# SC8815.net
KiCad netlist of a schematic drawn in Altium Designer
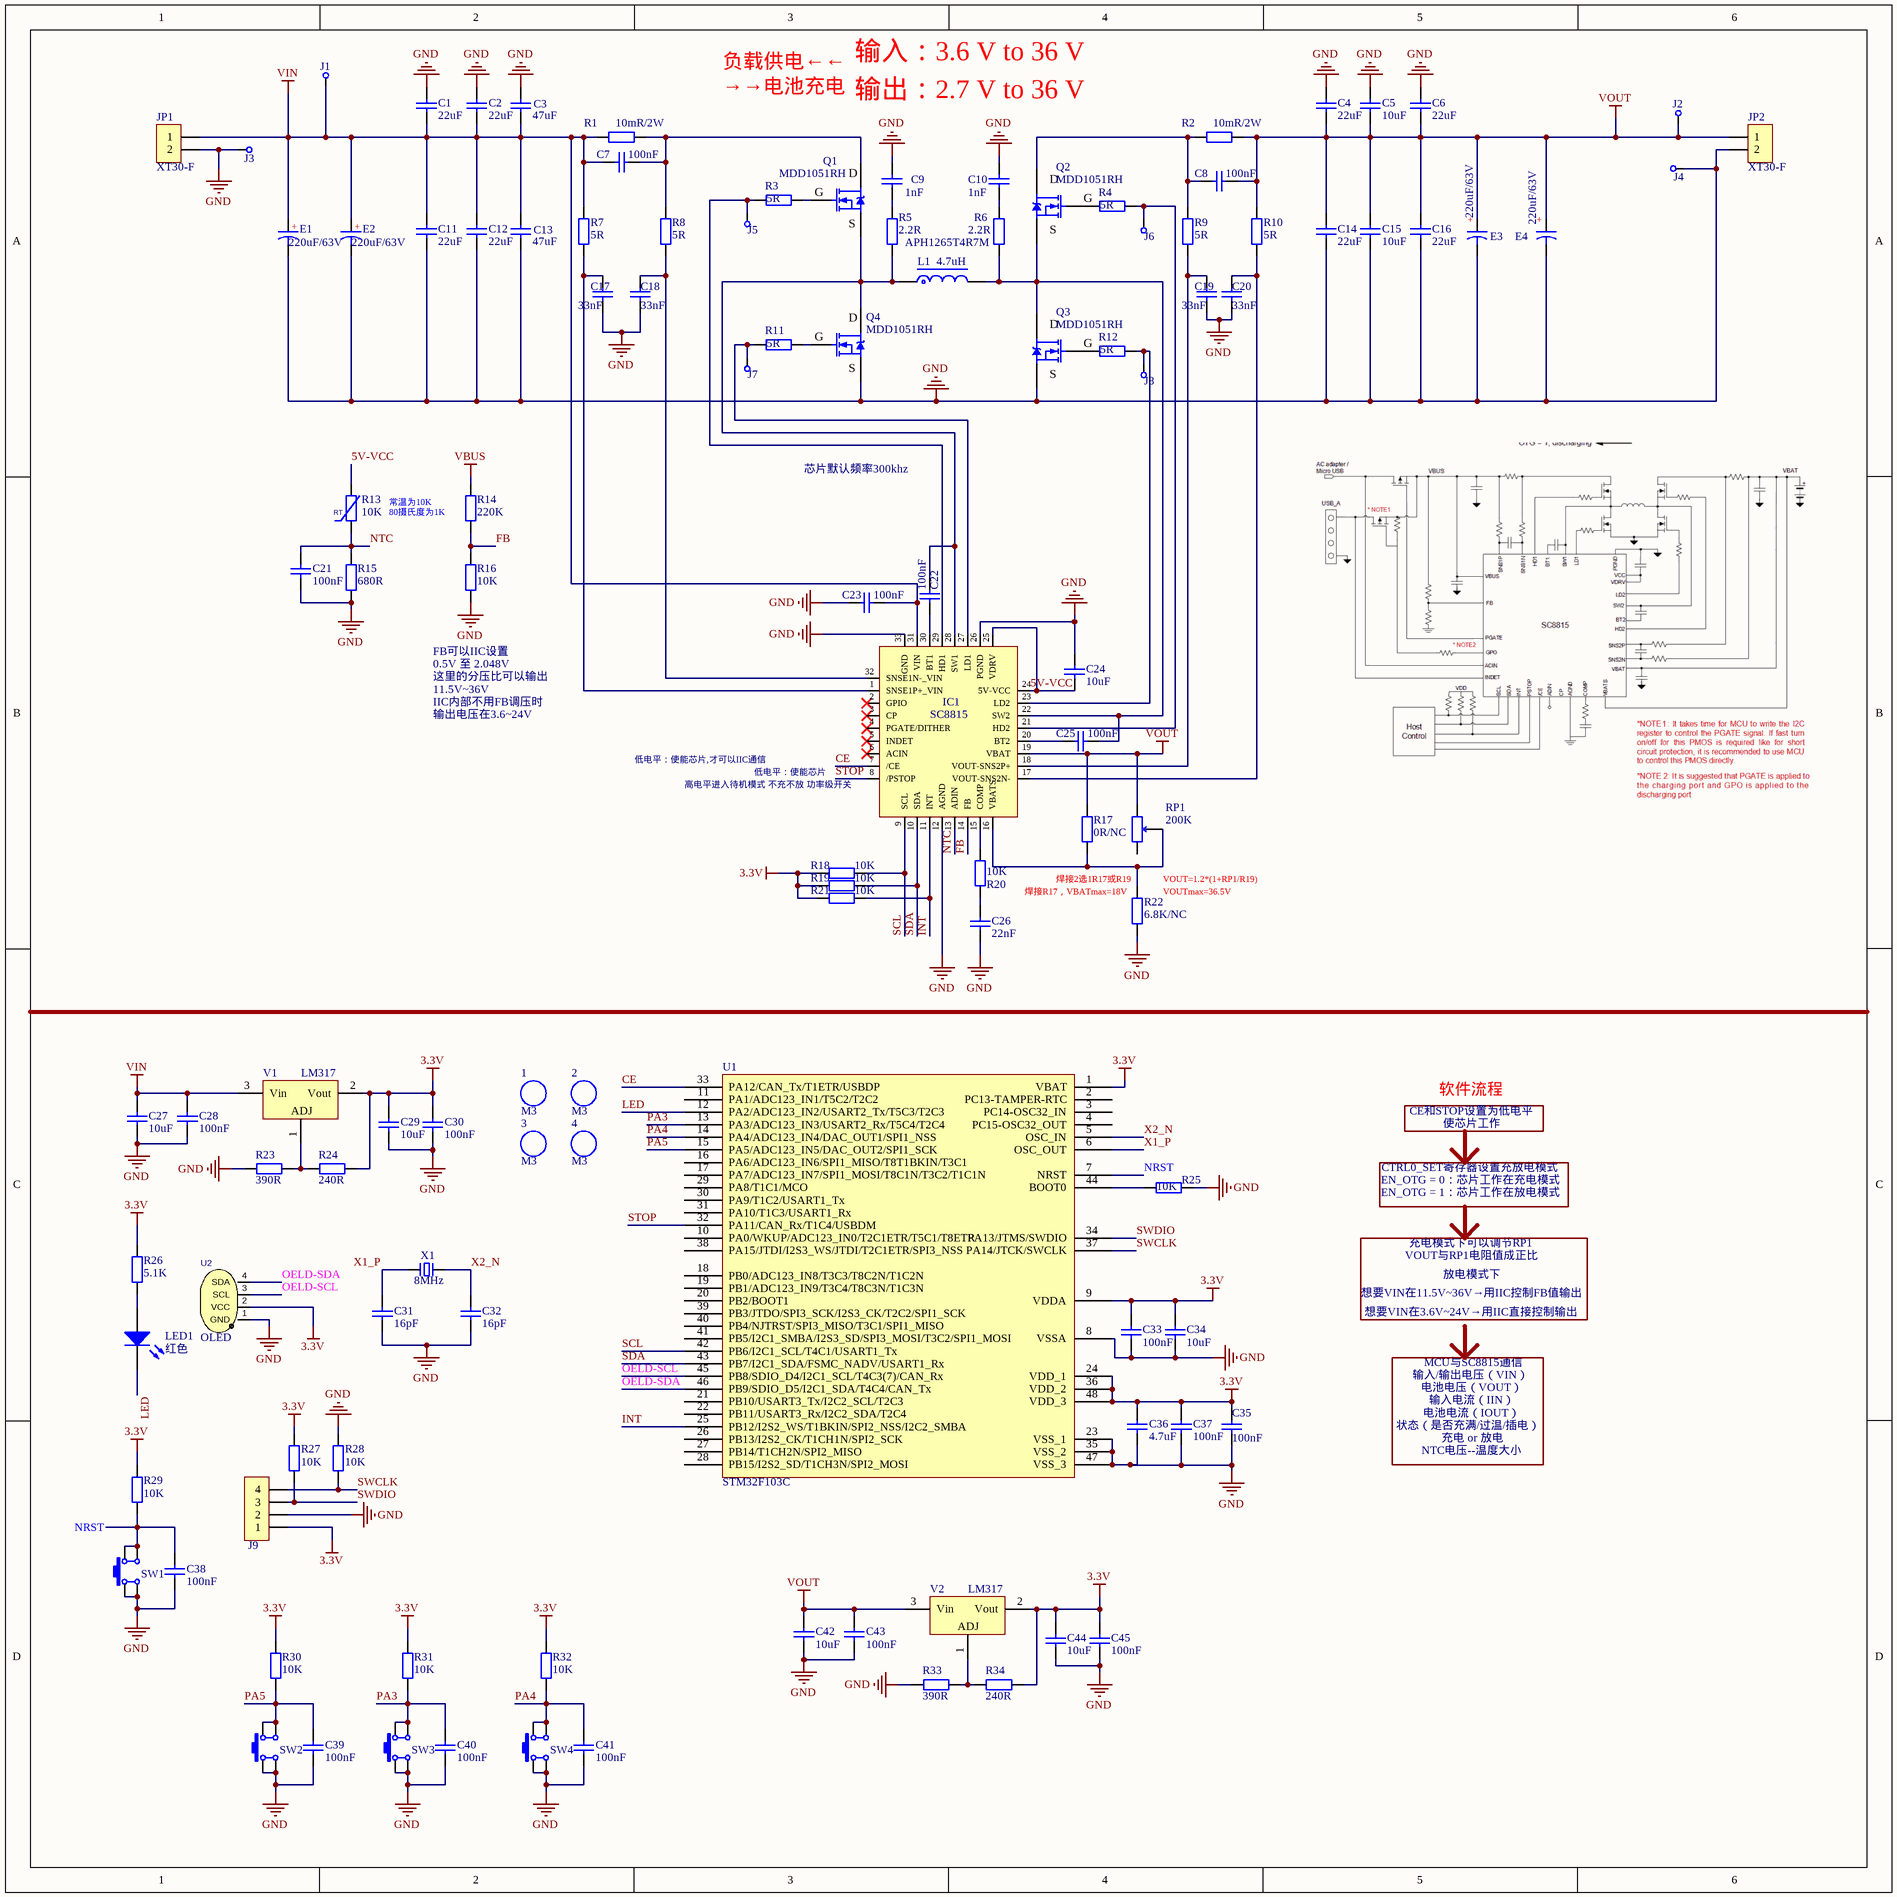
[diagram p0: SC8815.SchDoc]

(export (version "E")
  (design (tool "Eeschema 10.0.6"))
  (components
    (comp (ref "1")
      (value "M3")
      (footprint "M3 125X200")
      (description "铜柱孔")
      (libsource (lib "0.5 - 按键_开关_蜂鸣器_电池_测试点_Mark点_铜柱") (part "M3"))
    )
    (comp (ref "2")
      (value "M3")
      (footprint "M3 125X200")
      (description "铜柱孔")
      (libsource (lib "0.5 - 按键_开关_蜂鸣器_电池_测试点_Mark点_铜柱") (part "M3"))
    )
    (comp (ref "3")
      (value "M3")
      (footprint "M3 125X200")
      (description "铜柱孔")
      (libsource (lib "0.5 - 按键_开关_蜂鸣器_电池_测试点_Mark点_铜柱") (part "M3"))
    )
    (comp (ref "4")
      (value "M3")
      (footprint "M3 125X200")
      (description "铜柱孔")
      (libsource (lib "0.5 - 按键_开关_蜂鸣器_电池_测试点_Mark点_铜柱") (part "M3"))
    )
    (comp (ref "C1")
      (value "22uF")
      (footprint "C0805_L")
      (description "贴片电容/MLCC电容")
      (libsource (lib "0.1 - 电阻-电容-电感-保险丝-晶振-晶体-磁珠-电位器-法拉电容-馈通电容") (part "C"))
    )
    (comp (ref "C2")
      (value "22uF")
      (footprint "C0805_L")
      (description "贴片电容/MLCC电容")
      (libsource (lib "0.1 - 电阻-电容-电感-保险丝-晶振-晶体-磁珠-电位器-法拉电容-馈通电容") (part "C"))
    )
    (comp (ref "C3")
      (value "47uF")
      (footprint "C0805_L")
      (description "贴片电容/MLCC电容")
      (libsource (lib "0.1 - 电阻-电容-电感-保险丝-晶振-晶体-磁珠-电位器-法拉电容-馈通电容") (part "C"))
    )
    (comp (ref "C4")
      (value "22uF")
      (footprint "C0805_L")
      (description "贴片电容/MLCC电容")
      (libsource (lib "0.1 - 电阻-电容-电感-保险丝-晶振-晶体-磁珠-电位器-法拉电容-馈通电容") (part "C"))
    )
    (comp (ref "C5")
      (value "10uF")
      (footprint "C0805_L")
      (description "贴片电容/MLCC电容")
      (libsource (lib "0.1 - 电阻-电容-电感-保险丝-晶振-晶体-磁珠-电位器-法拉电容-馈通电容") (part "C"))
    )
    (comp (ref "C6")
      (value "22uF")
      (footprint "C0805_L")
      (description "贴片电容/MLCC电容")
      (libsource (lib "0.1 - 电阻-电容-电感-保险丝-晶振-晶体-磁珠-电位器-法拉电容-馈通电容") (part "C"))
    )
    (comp (ref "C7")
      (value "100nF")
      (footprint "C0805_L")
      (description "贴片电容/MLCC电容")
      (libsource (lib "0.1 - 电阻-电容-电感-保险丝-晶振-晶体-磁珠-电位器-法拉电容-馈通电容") (part "C"))
    )
    (comp (ref "C8")
      (value "100nF")
      (footprint "C0805_L")
      (description "贴片电容/MLCC电容")
      (libsource (lib "0.1 - 电阻-电容-电感-保险丝-晶振-晶体-磁珠-电位器-法拉电容-馈通电容") (part "C"))
    )
    (comp (ref "C9")
      (value "1nF")
      (footprint "C0805_L")
      (description "贴片电容/MLCC电容")
      (libsource (lib "0.1 - 电阻-电容-电感-保险丝-晶振-晶体-磁珠-电位器-法拉电容-馈通电容") (part "C"))
    )
    (comp (ref "C10")
      (value "1nF")
      (footprint "C0805_L")
      (description "贴片电容/MLCC电容")
      (libsource (lib "0.1 - 电阻-电容-电感-保险丝-晶振-晶体-磁珠-电位器-法拉电容-馈通电容") (part "C"))
    )
    (comp (ref "C11")
      (value "22uF")
      (footprint "C0805_L")
      (description "贴片电容/MLCC电容")
      (libsource (lib "0.1 - 电阻-电容-电感-保险丝-晶振-晶体-磁珠-电位器-法拉电容-馈通电容") (part "C"))
    )
    (comp (ref "C12")
      (value "22uF")
      (footprint "C0805_L")
      (description "贴片电容/MLCC电容")
      (libsource (lib "0.1 - 电阻-电容-电感-保险丝-晶振-晶体-磁珠-电位器-法拉电容-馈通电容") (part "C"))
    )
    (comp (ref "C13")
      (value "47uF")
      (footprint "C0805_L")
      (description "贴片电容/MLCC电容")
      (libsource (lib "0.1 - 电阻-电容-电感-保险丝-晶振-晶体-磁珠-电位器-法拉电容-馈通电容") (part "C"))
    )
    (comp (ref "C14")
      (value "22uF")
      (footprint "C0805_L")
      (description "贴片电容/MLCC电容")
      (libsource (lib "0.1 - 电阻-电容-电感-保险丝-晶振-晶体-磁珠-电位器-法拉电容-馈通电容") (part "C"))
    )
    (comp (ref "C15")
      (value "10uF")
      (footprint "C0805_L")
      (description "贴片电容/MLCC电容")
      (libsource (lib "0.1 - 电阻-电容-电感-保险丝-晶振-晶体-磁珠-电位器-法拉电容-馈通电容") (part "C"))
    )
    (comp (ref "C16")
      (value "22uF")
      (footprint "C0805_L")
      (description "贴片电容/MLCC电容")
      (libsource (lib "0.1 - 电阻-电容-电感-保险丝-晶振-晶体-磁珠-电位器-法拉电容-馈通电容") (part "C"))
    )
    (comp (ref "C17")
      (value "33nF")
      (footprint "C0805_L")
      (description "贴片电容/MLCC电容")
      (libsource (lib "0.1 - 电阻-电容-电感-保险丝-晶振-晶体-磁珠-电位器-法拉电容-馈通电容") (part "C"))
    )
    (comp (ref "C18")
      (value "33nF")
      (footprint "C0805_L")
      (description "贴片电容/MLCC电容")
      (libsource (lib "0.1 - 电阻-电容-电感-保险丝-晶振-晶体-磁珠-电位器-法拉电容-馈通电容") (part "C"))
    )
    (comp (ref "C19")
      (value "33nF")
      (footprint "C0805_L")
      (description "贴片电容/MLCC电容")
      (libsource (lib "0.1 - 电阻-电容-电感-保险丝-晶振-晶体-磁珠-电位器-法拉电容-馈通电容") (part "C"))
    )
    (comp (ref "C20")
      (value "33nF")
      (footprint "C0805_L")
      (description "贴片电容/MLCC电容")
      (libsource (lib "0.1 - 电阻-电容-电感-保险丝-晶振-晶体-磁珠-电位器-法拉电容-馈通电容") (part "C"))
    )
    (comp (ref "C21")
      (value "100nF")
      (footprint "C0805_L")
      (description "贴片电容/MLCC电容")
      (libsource (lib "0.1 - 电阻-电容-电感-保险丝-晶振-晶体-磁珠-电位器-法拉电容-馈通电容") (part "C"))
    )
    (comp (ref "C22")
      (value "100nF")
      (footprint "C0805_L")
      (description "贴片电容/MLCC电容")
      (libsource (lib "0.1 - 电阻-电容-电感-保险丝-晶振-晶体-磁珠-电位器-法拉电容-馈通电容") (part "C"))
    )
    (comp (ref "C23")
      (value "100nF")
      (footprint "C0805_L")
      (description "贴片电容/MLCC电容")
      (libsource (lib "0.1 - 电阻-电容-电感-保险丝-晶振-晶体-磁珠-电位器-法拉电容-馈通电容") (part "C"))
    )
    (comp (ref "C24")
      (value "10uF")
      (footprint "C0805_L")
      (description "贴片电容/MLCC电容")
      (libsource (lib "0.1 - 电阻-电容-电感-保险丝-晶振-晶体-磁珠-电位器-法拉电容-馈通电容") (part "C"))
    )
    (comp (ref "C25")
      (value "100nF")
      (footprint "C0805_L")
      (description "贴片电容/MLCC电容")
      (libsource (lib "0.1 - 电阻-电容-电感-保险丝-晶振-晶体-磁珠-电位器-法拉电容-馈通电容") (part "C"))
    )
    (comp (ref "C26")
      (value "22nF")
      (footprint "C0805_L")
      (description "贴片电容/MLCC电容")
      (libsource (lib "0.1 - 电阻-电容-电感-保险丝-晶振-晶体-磁珠-电位器-法拉电容-馈通电容") (part "C"))
    )
    (comp (ref "C27")
      (value "10uF")
      (footprint "C0805_L")
      (description "贴片电容/MLCC电容")
      (libsource (lib "0.1 - 电阻-电容-电感-保险丝-晶振-晶体-磁珠-电位器-法拉电容-馈通电容") (part "C"))
    )
    (comp (ref "C28")
      (value "100nF")
      (footprint "C0805_L")
      (description "贴片电容/MLCC电容")
      (libsource (lib "0.1 - 电阻-电容-电感-保险丝-晶振-晶体-磁珠-电位器-法拉电容-馈通电容") (part "C"))
    )
    (comp (ref "C29")
      (value "10uF")
      (footprint "C0805_L")
      (description "贴片电容/MLCC电容")
      (libsource (lib "0.1 - 电阻-电容-电感-保险丝-晶振-晶体-磁珠-电位器-法拉电容-馈通电容") (part "C"))
    )
    (comp (ref "C30")
      (value "100nF")
      (footprint "C0805_L")
      (description "贴片电容/MLCC电容")
      (libsource (lib "0.1 - 电阻-电容-电感-保险丝-晶振-晶体-磁珠-电位器-法拉电容-馈通电容") (part "C"))
    )
    (comp (ref "C31")
      (value "16pF")
      (footprint "C0805_L")
      (description "贴片电容/MLCC电容")
      (libsource (lib "0.1 - 电阻-电容-电感-保险丝-晶振-晶体-磁珠-电位器-法拉电容-馈通电容") (part "C"))
    )
    (comp (ref "C32")
      (value "16pF")
      (footprint "C0805_L")
      (description "贴片电容/MLCC电容")
      (libsource (lib "0.1 - 电阻-电容-电感-保险丝-晶振-晶体-磁珠-电位器-法拉电容-馈通电容") (part "C"))
    )
    (comp (ref "C33")
      (value "100nF")
      (footprint "C0805_L")
      (description "贴片电容/MLCC电容")
      (libsource (lib "0.1 - 电阻-电容-电感-保险丝-晶振-晶体-磁珠-电位器-法拉电容-馈通电容") (part "C"))
    )
    (comp (ref "C34")
      (value "10uF")
      (footprint "C0805_L")
      (description "贴片电容/MLCC电容")
      (libsource (lib "0.1 - 电阻-电容-电感-保险丝-晶振-晶体-磁珠-电位器-法拉电容-馈通电容") (part "C"))
    )
    (comp (ref "C35")
      (value "100nF")
      (footprint "C0805_L")
      (description "贴片电容/MLCC电容")
      (libsource (lib "0.1 - 电阻-电容-电感-保险丝-晶振-晶体-磁珠-电位器-法拉电容-馈通电容") (part "C"))
    )
    (comp (ref "C36")
      (value "4.7uF")
      (footprint "C0805_L")
      (description "贴片电容/MLCC电容")
      (libsource (lib "0.1 - 电阻-电容-电感-保险丝-晶振-晶体-磁珠-电位器-法拉电容-馈通电容") (part "C"))
    )
    (comp (ref "C37")
      (value "100nF")
      (footprint "C0805_L")
      (description "贴片电容/MLCC电容")
      (libsource (lib "0.1 - 电阻-电容-电感-保险丝-晶振-晶体-磁珠-电位器-法拉电容-馈通电容") (part "C"))
    )
    (comp (ref "C38")
      (value "100nF")
      (footprint "C0805_L")
      (description "贴片电容/MLCC电容")
      (libsource (lib "0.1 - 电阻-电容-电感-保险丝-晶振-晶体-磁珠-电位器-法拉电容-馈通电容") (part "C"))
    )
    (comp (ref "C39")
      (value "100nF")
      (footprint "C0805_L")
      (description "贴片电容/MLCC电容")
      (libsource (lib "0.1 - 电阻-电容-电感-保险丝-晶振-晶体-磁珠-电位器-法拉电容-馈通电容") (part "C"))
    )
    (comp (ref "C40")
      (value "100nF")
      (footprint "C0805_L")
      (description "贴片电容/MLCC电容")
      (libsource (lib "0.1 - 电阻-电容-电感-保险丝-晶振-晶体-磁珠-电位器-法拉电容-馈通电容") (part "C"))
    )
    (comp (ref "C41")
      (value "100nF")
      (footprint "C0805_L")
      (description "贴片电容/MLCC电容")
      (libsource (lib "0.1 - 电阻-电容-电感-保险丝-晶振-晶体-磁珠-电位器-法拉电容-馈通电容") (part "C"))
    )
    (comp (ref "C42")
      (value "10uF")
      (footprint "C0805_L")
      (description "贴片电容/MLCC电容")
      (libsource (lib "0.1 - 电阻-电容-电感-保险丝-晶振-晶体-磁珠-电位器-法拉电容-馈通电容") (part "C"))
    )
    (comp (ref "C43")
      (value "100nF")
      (footprint "C0805_L")
      (description "贴片电容/MLCC电容")
      (libsource (lib "0.1 - 电阻-电容-电感-保险丝-晶振-晶体-磁珠-电位器-法拉电容-馈通电容") (part "C"))
    )
    (comp (ref "C44")
      (value "10uF")
      (footprint "C0805_L")
      (description "贴片电容/MLCC电容")
      (libsource (lib "0.1 - 电阻-电容-电感-保险丝-晶振-晶体-磁珠-电位器-法拉电容-馈通电容") (part "C"))
    )
    (comp (ref "C45")
      (value "100nF")
      (footprint "C0805_L")
      (description "贴片电容/MLCC电容")
      (libsource (lib "0.1 - 电阻-电容-电感-保险丝-晶振-晶体-磁珠-电位器-法拉电容-馈通电容") (part "C"))
    )
    (comp (ref "E1")
      (value "220uF/63V")
      (footprint "CT 5.0*10*13 - R")
      (description "直插固态电容")
      (libsource (lib "0.1 - 电阻-电容-电感-保险丝-晶振-晶体-磁珠-电位器-法拉电容-馈通电容") (part "CS"))
    )
    (comp (ref "E2")
      (value "220uF/63V")
      (footprint "CT 5.0*10*13 - R")
      (description "直插固态电容")
      (libsource (lib "0.1 - 电阻-电容-电感-保险丝-晶振-晶体-磁珠-电位器-法拉电容-馈通电容") (part "CS"))
    )
    (comp (ref "E3")
      (value "220uF/63V")
      (footprint "CT 5.0*10*13 - R")
      (description "直插固态电容")
      (libsource (lib "") (part "CS_1"))
    )
    (comp (ref "E4")
      (value "220uF/63V")
      (footprint "CT 5.0*10*13 - R")
      (description "直插固态电容")
      (libsource (lib "") (part "CS_1"))
    )
    (comp (ref "IC1")
      (value "SC8815")
      (footprint "QFN32_L4.0-W4.0-P0.4")
      (description "双向同步升降压IC")
      (libsource (lib "0.7 - 电源类芯片") (part "SC8815"))
    )
    (comp (ref "J1")
      (value "CHECK")
      (footprint "CHECK-A")
      (description "测试点")
      (libsource (lib "课程库") (part "CHECK"))
    )
    (comp (ref "J2")
      (value "CHECK")
      (footprint "CHECK-A")
      (description "测试点")
      (libsource (lib "课程库") (part "CHECK"))
    )
    (comp (ref "J3")
      (value "CHECK")
      (footprint "CHECK-A")
      (description "测试点")
      (libsource (lib "课程库") (part "CHECK"))
    )
    (comp (ref "J4")
      (value "CHECK")
      (footprint "CHECK-A")
      (description "测试点")
      (libsource (lib "课程库") (part "CHECK"))
    )
    (comp (ref "J5")
      (value "CHECK")
      (footprint "CHECK-A")
      (description "测试点")
      (libsource (lib "课程库") (part "CHECK"))
    )
    (comp (ref "J6")
      (value "CHECK")
      (footprint "CHECK-A")
      (description "测试点")
      (libsource (lib "课程库") (part "CHECK"))
    )
    (comp (ref "J7")
      (value "CHECK")
      (footprint "CHECK-A")
      (description "测试点")
      (libsource (lib "课程库") (part "CHECK"))
    )
    (comp (ref "J8")
      (value "CHECK")
      (footprint "CHECK-A")
      (description "测试点")
      (libsource (lib "课程库") (part "CHECK"))
    )
    (comp (ref "J9")
      (value "HDR-1X4")
      (footprint "HDR2.54-LI-4P")
      (description "4P接插件")
      (libsource (lib "5.5 - 2.54mm连接器(KF2EDGK_XH2.54_2.54排针排母)") (part "Header 4"))
    )
    (comp (ref "JP1")
      (value "XT30-F")
      (footprint "XT30PW-F")
      (description "XT30母座")
      (libsource (lib "") (part "XT30-F_1"))
    )
    (comp (ref "JP2")
      (value "XT30-F")
      (footprint "XT30PW-F")
      (description "XT30母座")
      (libsource (lib "0.6 - 电源_音频_USB Type-C_HDMI_XT60_5557_D-SUB_RJ45_SD-TF_SIM插座") (part "XT30-F"))
    )
    (comp (ref "L1")
      (value "4.7uH")
      (footprint "SMD,13.5x12.6mm")
      (description "一体成型电感")
      (libsource (lib "0.1 - 电阻-电容-电感-保险丝-晶振-晶体-磁珠-电位器-法拉电容-馈通电容") (part "L-Molding Choke"))
    )
    (comp (ref "LED1")
      (value "红色")
      (footprint "LED0805_G")
      (description "贴片LED")
      (libsource (lib "0.3 - LED发光二极管-IR二极管_接收管-光耦") (part "LED"))
    )
    (comp (ref "Q1")
      (value "MDD1051RH")
      (footprint "TO252")
      (description "N沟道 30V/80A")
      (libsource (lib "0.4 - 三极管-场效应管-可控硅") (part "NCE3080"))
    )
    (comp (ref "Q2")
      (value "MDD1051RH")
      (footprint "TO252")
      (description "N沟道 30V/80A")
      (libsource (lib "0.4 - 三极管-场效应管-可控硅") (part "NCE3080"))
    )
    (comp (ref "Q3")
      (value "MDD1051RH")
      (footprint "TO252")
      (description "N沟道 30V/80A")
      (libsource (lib "0.4 - 三极管-场效应管-可控硅") (part "NCE3080"))
    )
    (comp (ref "Q4")
      (value "MDD1051RH")
      (footprint "TO252")
      (description "N沟道 30V/80A")
      (libsource (lib "0.4 - 三极管-场效应管-可控硅") (part "NCE3080"))
    )
    (comp (ref "R1")
      (value "10mR/2W")
      (footprint "R2512_M")
      (description "贴片电阻")
      (libsource (lib "0.1 - 电阻-电容-电感-保险丝-晶振-晶体-磁珠-电位器-法拉电容-馈通电容") (part "R"))
    )
    (comp (ref "R2")
      (value "10mR/2W")
      (footprint "R2512_M")
      (description "贴片电阻")
      (libsource (lib "0.1 - 电阻-电容-电感-保险丝-晶振-晶体-磁珠-电位器-法拉电容-馈通电容") (part "R"))
    )
    (comp (ref "R3")
      (value "5R")
      (footprint "R0805_L")
      (description "贴片电阻")
      (libsource (lib "0.1 - 电阻-电容-电感-保险丝-晶振-晶体-磁珠-电位器-法拉电容-馈通电容") (part "R"))
    )
    (comp (ref "R4")
      (value "5R")
      (footprint "R0805_L")
      (description "贴片电阻")
      (libsource (lib "0.1 - 电阻-电容-电感-保险丝-晶振-晶体-磁珠-电位器-法拉电容-馈通电容") (part "R"))
    )
    (comp (ref "R5")
      (value "2.2R")
      (footprint "R0805_L")
      (description "贴片电阻")
      (libsource (lib "0.1 - 电阻-电容-电感-保险丝-晶振-晶体-磁珠-电位器-法拉电容-馈通电容") (part "R"))
    )
    (comp (ref "R6")
      (value "2.2R")
      (footprint "R0805_L")
      (description "贴片电阻")
      (libsource (lib "0.1 - 电阻-电容-电感-保险丝-晶振-晶体-磁珠-电位器-法拉电容-馈通电容") (part "R"))
    )
    (comp (ref "R7")
      (value "5R")
      (footprint "R0805_L")
      (description "贴片电阻")
      (libsource (lib "0.1 - 电阻-电容-电感-保险丝-晶振-晶体-磁珠-电位器-法拉电容-馈通电容") (part "R"))
    )
    (comp (ref "R8")
      (value "5R")
      (footprint "R0805_L")
      (description "贴片电阻")
      (libsource (lib "0.1 - 电阻-电容-电感-保险丝-晶振-晶体-磁珠-电位器-法拉电容-馈通电容") (part "R"))
    )
    (comp (ref "R9")
      (value "5R")
      (footprint "R0805_L")
      (description "贴片电阻")
      (libsource (lib "0.1 - 电阻-电容-电感-保险丝-晶振-晶体-磁珠-电位器-法拉电容-馈通电容") (part "R"))
    )
    (comp (ref "R10")
      (value "5R")
      (footprint "R0805_L")
      (description "贴片电阻")
      (libsource (lib "0.1 - 电阻-电容-电感-保险丝-晶振-晶体-磁珠-电位器-法拉电容-馈通电容") (part "R"))
    )
    (comp (ref "R11")
      (value "5R")
      (footprint "R0805_L")
      (description "贴片电阻")
      (libsource (lib "0.1 - 电阻-电容-电感-保险丝-晶振-晶体-磁珠-电位器-法拉电容-馈通电容") (part "R"))
    )
    (comp (ref "R12")
      (value "5R")
      (footprint "R0805_L")
      (description "贴片电阻")
      (libsource (lib "0.1 - 电阻-电容-电感-保险丝-晶振-晶体-磁珠-电位器-法拉电容-馈通电容") (part "R"))
    )
    (comp (ref "R13")
      (value "10K")
      (footprint "R0805-HP_L")
      (description "热敏电阻")
      (libsource (lib "0.1 - 电阻-电容-电感-保险丝-晶振-晶体-磁珠-电位器-法拉电容-馈通电容") (part "RT"))
    )
    (comp (ref "R14")
      (value "220K")
      (footprint "R0805_L")
      (description "贴片电阻")
      (libsource (lib "0.1 - 电阻-电容-电感-保险丝-晶振-晶体-磁珠-电位器-法拉电容-馈通电容") (part "R"))
    )
    (comp (ref "R15")
      (value "680R")
      (footprint "R0805_L")
      (description "贴片电阻")
      (libsource (lib "0.1 - 电阻-电容-电感-保险丝-晶振-晶体-磁珠-电位器-法拉电容-馈通电容") (part "R"))
    )
    (comp (ref "R16")
      (value "10K")
      (footprint "R0805_L")
      (description "贴片电阻")
      (libsource (lib "0.1 - 电阻-电容-电感-保险丝-晶振-晶体-磁珠-电位器-法拉电容-馈通电容") (part "R"))
    )
    (comp (ref "R17")
      (value "0R/NC")
      (footprint "R0805_L")
      (description "贴片电阻")
      (libsource (lib "0.1 - 电阻-电容-电感-保险丝-晶振-晶体-磁珠-电位器-法拉电容-馈通电容") (part "R"))
    )
    (comp (ref "R18")
      (value "10K")
      (footprint "R0805_L")
      (description "贴片电阻")
      (libsource (lib "0.1 - 电阻-电容-电感-保险丝-晶振-晶体-磁珠-电位器-法拉电容-馈通电容") (part "R"))
    )
    (comp (ref "R19")
      (value "10K")
      (footprint "R0805_L")
      (description "贴片电阻")
      (libsource (lib "0.1 - 电阻-电容-电感-保险丝-晶振-晶体-磁珠-电位器-法拉电容-馈通电容") (part "R"))
    )
    (comp (ref "R20")
      (value "10K")
      (footprint "R0805_L")
      (description "贴片电阻")
      (libsource (lib "0.1 - 电阻-电容-电感-保险丝-晶振-晶体-磁珠-电位器-法拉电容-馈通电容") (part "R"))
    )
    (comp (ref "R21")
      (value "10K")
      (footprint "R0805_L")
      (description "贴片电阻")
      (libsource (lib "0.1 - 电阻-电容-电感-保险丝-晶振-晶体-磁珠-电位器-法拉电容-馈通电容") (part "R"))
    )
    (comp (ref "R22")
      (value "6.8K/NC")
      (footprint "R0805_L")
      (description "贴片电阻")
      (libsource (lib "0.1 - 电阻-电容-电感-保险丝-晶振-晶体-磁珠-电位器-法拉电容-馈通电容") (part "R"))
    )
    (comp (ref "R23")
      (value "390R")
      (footprint "R0805_L")
      (description "贴片电阻")
      (libsource (lib "0.1 - 电阻-电容-电感-保险丝-晶振-晶体-磁珠-电位器-法拉电容-馈通电容") (part "R"))
    )
    (comp (ref "R24")
      (value "240R")
      (footprint "R0805_L")
      (description "贴片电阻")
      (libsource (lib "0.1 - 电阻-电容-电感-保险丝-晶振-晶体-磁珠-电位器-法拉电容-馈通电容") (part "R"))
    )
    (comp (ref "R25")
      (value "10K")
      (footprint "R0805_L")
      (description "贴片电阻")
      (libsource (lib "0.1 - 电阻-电容-电感-保险丝-晶振-晶体-磁珠-电位器-法拉电容-馈通电容") (part "R"))
    )
    (comp (ref "R26")
      (value "5.1K")
      (footprint "R0805_L")
      (description "贴片电阻")
      (libsource (lib "0.1 - 电阻-电容-电感-保险丝-晶振-晶体-磁珠-电位器-法拉电容-馈通电容") (part "R"))
    )
    (comp (ref "R27")
      (value "10K")
      (footprint "R0805_L")
      (description "贴片电阻")
      (libsource (lib "0.1 - 电阻-电容-电感-保险丝-晶振-晶体-磁珠-电位器-法拉电容-馈通电容") (part "R"))
    )
    (comp (ref "R28")
      (value "10K")
      (footprint "R0805_L")
      (description "贴片电阻")
      (libsource (lib "0.1 - 电阻-电容-电感-保险丝-晶振-晶体-磁珠-电位器-法拉电容-馈通电容") (part "R"))
    )
    (comp (ref "R29")
      (value "10K")
      (footprint "R0805_L")
      (description "贴片电阻")
      (libsource (lib "0.1 - 电阻-电容-电感-保险丝-晶振-晶体-磁珠-电位器-法拉电容-馈通电容") (part "R"))
    )
    (comp (ref "R30")
      (value "10K")
      (footprint "R0805_L")
      (description "贴片电阻")
      (libsource (lib "0.1 - 电阻-电容-电感-保险丝-晶振-晶体-磁珠-电位器-法拉电容-馈通电容") (part "R"))
    )
    (comp (ref "R31")
      (value "10K")
      (footprint "R0805_L")
      (description "贴片电阻")
      (libsource (lib "0.1 - 电阻-电容-电感-保险丝-晶振-晶体-磁珠-电位器-法拉电容-馈通电容") (part "R"))
    )
    (comp (ref "R32")
      (value "10K")
      (footprint "R0805_L")
      (description "贴片电阻")
      (libsource (lib "0.1 - 电阻-电容-电感-保险丝-晶振-晶体-磁珠-电位器-法拉电容-馈通电容") (part "R"))
    )
    (comp (ref "R33")
      (value "390R")
      (footprint "R0805_L")
      (description "贴片电阻")
      (libsource (lib "0.1 - 电阻-电容-电感-保险丝-晶振-晶体-磁珠-电位器-法拉电容-馈通电容") (part "R"))
    )
    (comp (ref "R34")
      (value "240R")
      (footprint "R0805_L")
      (description "贴片电阻")
      (libsource (lib "0.1 - 电阻-电容-电感-保险丝-晶振-晶体-磁珠-电位器-法拉电容-馈通电容") (part "R"))
    )
    (comp (ref "RP1")
      (value "200K")
      (footprint "3296W")
      (description "单联电位器")
      (libsource (lib "0.1 - 电阻-电容-电感-保险丝-晶振-晶体-磁珠-电位器-法拉电容-馈通电容") (part "RP"))
    )
    (comp (ref "SW1")
      (value "4.5x4.5x3.8")
      (footprint "SW SMD-4.5*4.5*3.8")
      (description "贴片4.5x4.5轻触开关")
      (libsource (lib "0.5 - 按键_开关_蜂鸣器_电池_测试点_Mark点_铜柱") (part "SW SMD-4.5x4.5"))
    )
    (comp (ref "SW2")
      (value "4.5x4.5x3.8")
      (footprint "SW SMD-4.5*4.5*3.8")
      (description "贴片4.5x4.5轻触开关")
      (libsource (lib "0.5 - 按键_开关_蜂鸣器_电池_测试点_Mark点_铜柱") (part "SW SMD-4.5x4.5"))
    )
    (comp (ref "SW3")
      (value "4.5x4.5x3.8")
      (footprint "SW SMD-4.5*4.5*3.8")
      (description "贴片4.5x4.5轻触开关")
      (libsource (lib "0.5 - 按键_开关_蜂鸣器_电池_测试点_Mark点_铜柱") (part "SW SMD-4.5x4.5"))
    )
    (comp (ref "SW4")
      (value "4.5x4.5x3.8")
      (footprint "SW SMD-4.5*4.5*3.8")
      (description "贴片4.5x4.5轻触开关")
      (libsource (lib "0.5 - 按键_开关_蜂鸣器_电池_测试点_Mark点_铜柱") (part "SW SMD-4.5x4.5"))
    )
    (comp (ref "U1")
      (value "STM32F103C")
      (footprint "LQFP-48_M")
      (description "STM32单片机48引脚")
      (libsource (lib "课程库") (part "STM32F103C"))
    )
    (comp (ref "U2")
      (value "OLED")
      (footprint "OLED")
      (description "0.96OLED")
      (libsource (lib "课程库") (part "OLED"))
    )
    (comp (ref "V1")
      (value "LM317")
      (footprint "SOT223_M")
      (description "可调线性稳压芯片")
      (libsource (lib "0.7 - 电源类芯片") (part "LM317"))
    )
    (comp (ref "V2")
      (value "LM317")
      (footprint "SOT223_M")
      (description "可调线性稳压芯片")
      (libsource (lib "0.7 - 电源类芯片") (part "LM317"))
    )
    (comp (ref "X1")
      (value "8MHz")
      (footprint "XTAL-5032-2P")
      (description "2脚无源晶振(谐振器）")
      (libsource (lib "0.1 - 电阻-电容-电感-保险丝-晶振-晶体-磁珠-电位器-法拉电容-馈通电容") (part "XTAL-2P"))
    )
  )
  (nets
    (net (code "1") (name "/5V-VCC") (class "Default")
      (node (ref "C24") (pin "2") (pinfunction "2_2") (pintype "passive"))
      (node (ref "IC1") (pin "24") (pinfunction "5V-VCC_24") (pintype "passive"))
      (node (ref "IC1") (pin "25") (pinfunction "VDRV_25") (pintype "passive"))
      (node (ref "R13") (pin "2") (pinfunction "2_2") (pintype "passive"))
    )
    (net (code "2") (name "/CE") (class "Default")
      (node (ref "IC1") (pin "7") (pinfunction "/CE_7") (pintype "passive"))
      (node (ref "U1") (pin "33") (pinfunction "PA12/CAN_Tx/T1ETR/USBDP_33") (pintype "passive"))
    )
    (net (code "3") (name "/FB") (class "Default")
      (node (ref "IC1") (pin "14") (pinfunction "FB_14") (pintype "passive"))
      (node (ref "R14") (pin "2") (pinfunction "2_2") (pintype "passive"))
      (node (ref "R16") (pin "1") (pinfunction "1_1") (pintype "passive"))
    )
    (net (code "4") (name "/INT") (class "Default")
      (node (ref "IC1") (pin "11") (pinfunction "INT_11") (pintype "passive"))
      (node (ref "R21") (pin "2") (pinfunction "2_2") (pintype "passive"))
      (node (ref "U1") (pin "25") (pinfunction "PB12/I2S2_WS/T1BKIN/SPI2_NSS/I2C2_SMBA_25") (pintype "passive"))
    )
    (net (code "5") (name "/LED") (class "Default")
      (node (ref "LED1") (pin "2") (pinfunction "K_2") (pintype "passive"))
      (node (ref "U1") (pin "12") (pinfunction "PA2/ADC123_IN2/USART2_Tx/T5C3/T2C3_12") (pintype "passive"))
    )
    (net (code "6") (name "/NRST") (class "Default")
      (node (ref "C38") (pin "2") (pinfunction "2_2") (pintype "passive"))
      (node (ref "R29") (pin "2") (pinfunction "2_2") (pintype "passive"))
      (node (ref "SW1") (pin "2") (pinfunction "2_2") (pintype "passive"))
      (node (ref "SW1") (pin "3") (pinfunction "3_3") (pintype "passive"))
      (node (ref "U1") (pin "7") (pinfunction "NRST_7") (pintype "passive"))
    )
    (net (code "7") (name "/NTC") (class "Default")
      (node (ref "C21") (pin "1") (pinfunction "1_1") (pintype "passive"))
      (node (ref "IC1") (pin "13") (pinfunction "ADIN_13") (pintype "passive"))
      (node (ref "R13") (pin "1") (pinfunction "1_1") (pintype "passive"))
      (node (ref "R15") (pin "1") (pinfunction "1_1") (pintype "passive"))
    )
    (net (code "8") (name "/OELD-SCL") (class "Default")
      (node (ref "U1") (pin "45") (pinfunction "PB8/SDIO_D4/I2C1_SCL/T4C3(7)/CAN_Rx_45") (pintype "passive"))
      (node (ref "U2") (pin "3") (pinfunction "SCL_3") (pintype "passive"))
    )
    (net (code "9") (name "/OELD-SDA") (class "Default")
      (node (ref "U1") (pin "46") (pinfunction "PB9/SDIO_D5/I2C1_SDA/T4C4/CAN_Tx_46") (pintype "passive"))
      (node (ref "U2") (pin "4") (pinfunction "SDA_4") (pintype "passive"))
    )
    (net (code "10") (name "/PA3") (class "Default")
      (node (ref "C40") (pin "2") (pinfunction "2_2") (pintype "passive"))
      (node (ref "R31") (pin "2") (pinfunction "2_2") (pintype "passive"))
      (node (ref "SW3") (pin "2") (pinfunction "2_2") (pintype "passive"))
      (node (ref "SW3") (pin "3") (pinfunction "3_3") (pintype "passive"))
      (node (ref "U1") (pin "13") (pinfunction "PA3/ADC123_IN3/USART2_Rx/T5C4/T2C4_13") (pintype "passive"))
    )
    (net (code "11") (name "/PA4") (class "Default")
      (node (ref "C41") (pin "2") (pinfunction "2_2") (pintype "passive"))
      (node (ref "R32") (pin "2") (pinfunction "2_2") (pintype "passive"))
      (node (ref "SW4") (pin "2") (pinfunction "2_2") (pintype "passive"))
      (node (ref "SW4") (pin "3") (pinfunction "3_3") (pintype "passive"))
      (node (ref "U1") (pin "14") (pinfunction "PA4/ADC123_IN4/DAC_OUT1/SPI1_NSS_14") (pintype "passive"))
    )
    (net (code "12") (name "/PA5") (class "Default")
      (node (ref "C39") (pin "2") (pinfunction "2_2") (pintype "passive"))
      (node (ref "R30") (pin "2") (pinfunction "2_2") (pintype "passive"))
      (node (ref "SW2") (pin "2") (pinfunction "2_2") (pintype "passive"))
      (node (ref "SW2") (pin "3") (pinfunction "3_3") (pintype "passive"))
      (node (ref "U1") (pin "15") (pinfunction "PA5/ADC123_IN5/DAC_OUT2/SPI1_SCK_15") (pintype "passive"))
    )
    (net (code "13") (name "/SCL") (class "Default")
      (node (ref "IC1") (pin "9") (pinfunction "SCL_9") (pintype "passive"))
      (node (ref "R18") (pin "2") (pinfunction "2_2") (pintype "passive"))
      (node (ref "U1") (pin "42") (pinfunction "PB6/I2C1_SCL/T4C1/USART1_Tx_42") (pintype "passive"))
    )
    (net (code "14") (name "/SDA") (class "Default")
      (node (ref "IC1") (pin "10") (pinfunction "SDA_10") (pintype "passive"))
      (node (ref "R19") (pin "2") (pinfunction "2_2") (pintype "passive"))
      (node (ref "U1") (pin "43") (pinfunction "PB7/I2C1_SDA/FSMC_NADV/USART1_Rx_43") (pintype "passive"))
    )
    (net (code "15") (name "/STOP") (class "Default")
      (node (ref "IC1") (pin "8") (pinfunction "/PSTOP_8") (pintype "passive"))
      (node (ref "U1") (pin "32") (pinfunction "PA11/CAN_Rx/T1C4/USBDM_32") (pintype "passive"))
    )
    (net (code "16") (name "/SWCLK") (class "Default")
      (node (ref "J9") (pin "4") (pinfunction "4_4") (pintype "passive"))
      (node (ref "R28") (pin "2") (pinfunction "2_2") (pintype "passive"))
      (node (ref "U1") (pin "37") (pinfunction "PA14/JTCK/SWCLK_37") (pintype "passive"))
    )
    (net (code "17") (name "/SWDIO") (class "Default")
      (node (ref "J9") (pin "3") (pinfunction "3_3") (pintype "passive"))
      (node (ref "R27") (pin "2") (pinfunction "2_2") (pintype "passive"))
      (node (ref "U1") (pin "34") (pinfunction "PA13/JTMS/SWDIO_34") (pintype "passive"))
    )
    (net (code "18") (name "/X1_P") (class "Default")
      (node (ref "C31") (pin "2") (pinfunction "2_2") (pintype "passive"))
      (node (ref "U1") (pin "6") (pinfunction "OSC_OUT_6") (pintype "passive"))
      (node (ref "X1") (pin "1") (pinfunction "1_1") (pintype "passive"))
    )
    (net (code "19") (name "/X2_N") (class "Default")
      (node (ref "C32") (pin "2") (pinfunction "2_2") (pintype "passive"))
      (node (ref "U1") (pin "5") (pinfunction "OSC_IN_5") (pintype "passive"))
      (node (ref "X1") (pin "2") (pinfunction "2_2") (pintype "passive"))
    )
    (net (code "20") (name "3.3V") (class "Default")
      (node (ref "C29") (pin "2") (pinfunction "2_2") (pintype "passive"))
      (node (ref "C30") (pin "2") (pinfunction "2_2") (pintype "passive"))
      (node (ref "C33") (pin "2") (pinfunction "2_2") (pintype "passive"))
      (node (ref "C34") (pin "2") (pinfunction "2_2") (pintype "passive"))
      (node (ref "C35") (pin "2") (pinfunction "2_2") (pintype "passive"))
      (node (ref "C36") (pin "2") (pinfunction "2_2") (pintype "passive"))
      (node (ref "C37") (pin "2") (pinfunction "2_2") (pintype "passive"))
      (node (ref "C44") (pin "2") (pinfunction "2_2") (pintype "passive"))
      (node (ref "C45") (pin "2") (pinfunction "2_2") (pintype "passive"))
      (node (ref "J9") (pin "1") (pinfunction "1_1") (pintype "passive"))
      (node (ref "R18") (pin "1") (pinfunction "1_1") (pintype "passive"))
      (node (ref "R19") (pin "1") (pinfunction "1_1") (pintype "passive"))
      (node (ref "R21") (pin "1") (pinfunction "1_1") (pintype "passive"))
      (node (ref "R24") (pin "2") (pinfunction "2_2") (pintype "passive"))
      (node (ref "R26") (pin "1") (pinfunction "1_1") (pintype "passive"))
      (node (ref "R27") (pin "1") (pinfunction "1_1") (pintype "passive"))
      (node (ref "R29") (pin "1") (pinfunction "1_1") (pintype "passive"))
      (node (ref "R30") (pin "1") (pinfunction "1_1") (pintype "passive"))
      (node (ref "R31") (pin "1") (pinfunction "1_1") (pintype "passive"))
      (node (ref "R32") (pin "1") (pinfunction "1_1") (pintype "passive"))
      (node (ref "R34") (pin "2") (pinfunction "2_2") (pintype "passive"))
      (node (ref "U1") (pin "1") (pinfunction "VBAT_1") (pintype "passive"))
      (node (ref "U1") (pin "24") (pinfunction "VDD_1_24") (pintype "passive"))
      (node (ref "U1") (pin "36") (pinfunction "VDD_2_36") (pintype "passive"))
      (node (ref "U1") (pin "48") (pinfunction "VDD_3_48") (pintype "passive"))
      (node (ref "U1") (pin "9") (pinfunction "VDDA_9") (pintype "passive"))
      (node (ref "U2") (pin "2") (pinfunction "VCC_2") (pintype "passive"))
      (node (ref "V1") (pin "2") (pinfunction "Vout_2") (pintype "passive"))
      (node (ref "V2") (pin "2") (pinfunction "Vout_2") (pintype "passive"))
    )
    (net (code "21") (name "GND") (class "Default")
      (node (ref "C1") (pin "2") (pinfunction "2_2") (pintype "passive"))
      (node (ref "C10") (pin "1") (pinfunction "1_1") (pintype "passive"))
      (node (ref "C11") (pin "1") (pinfunction "1_1") (pintype "passive"))
      (node (ref "C12") (pin "1") (pinfunction "1_1") (pintype "passive"))
      (node (ref "C13") (pin "1") (pinfunction "1_1") (pintype "passive"))
      (node (ref "C14") (pin "1") (pinfunction "1_1") (pintype "passive"))
      (node (ref "C15") (pin "1") (pinfunction "1_1") (pintype "passive"))
      (node (ref "C16") (pin "1") (pinfunction "1_1") (pintype "passive"))
      (node (ref "C17") (pin "2") (pinfunction "2_2") (pintype "passive"))
      (node (ref "C18") (pin "2") (pinfunction "2_2") (pintype "passive"))
      (node (ref "C19") (pin "2") (pinfunction "2_2") (pintype "passive"))
      (node (ref "C2") (pin "2") (pinfunction "2_2") (pintype "passive"))
      (node (ref "C20") (pin "2") (pinfunction "2_2") (pintype "passive"))
      (node (ref "C21") (pin "2") (pinfunction "2_2") (pintype "passive"))
      (node (ref "C23") (pin "2") (pinfunction "2_2") (pintype "passive"))
      (node (ref "C24") (pin "1") (pinfunction "1_1") (pintype "passive"))
      (node (ref "C26") (pin "2") (pinfunction "2_2") (pintype "passive"))
      (node (ref "C27") (pin "1") (pinfunction "1_1") (pintype "passive"))
      (node (ref "C28") (pin "1") (pinfunction "1_1") (pintype "passive"))
      (node (ref "C29") (pin "1") (pinfunction "1_1") (pintype "passive"))
      (node (ref "C3") (pin "2") (pinfunction "2_2") (pintype "passive"))
      (node (ref "C30") (pin "1") (pinfunction "1_1") (pintype "passive"))
      (node (ref "C31") (pin "1") (pinfunction "1_1") (pintype "passive"))
      (node (ref "C32") (pin "1") (pinfunction "1_1") (pintype "passive"))
      (node (ref "C33") (pin "1") (pinfunction "1_1") (pintype "passive"))
      (node (ref "C34") (pin "1") (pinfunction "1_1") (pintype "passive"))
      (node (ref "C35") (pin "1") (pinfunction "1_1") (pintype "passive"))
      (node (ref "C36") (pin "1") (pinfunction "1_1") (pintype "passive"))
      (node (ref "C37") (pin "1") (pinfunction "1_1") (pintype "passive"))
      (node (ref "C38") (pin "1") (pinfunction "1_1") (pintype "passive"))
      (node (ref "C39") (pin "1") (pinfunction "1_1") (pintype "passive"))
      (node (ref "C4") (pin "2") (pinfunction "2_2") (pintype "passive"))
      (node (ref "C40") (pin "1") (pinfunction "1_1") (pintype "passive"))
      (node (ref "C41") (pin "1") (pinfunction "1_1") (pintype "passive"))
      (node (ref "C42") (pin "1") (pinfunction "1_1") (pintype "passive"))
      (node (ref "C43") (pin "1") (pinfunction "1_1") (pintype "passive"))
      (node (ref "C44") (pin "1") (pinfunction "1_1") (pintype "passive"))
      (node (ref "C45") (pin "1") (pinfunction "1_1") (pintype "passive"))
      (node (ref "C5") (pin "2") (pinfunction "2_2") (pintype "passive"))
      (node (ref "C6") (pin "2") (pinfunction "2_2") (pintype "passive"))
      (node (ref "C9") (pin "1") (pinfunction "1_1") (pintype "passive"))
      (node (ref "E1") (pin "2") (pinfunction "2_2") (pintype "passive"))
      (node (ref "E2") (pin "2") (pinfunction "2_2") (pintype "passive"))
      (node (ref "E3") (pin "2") (pinfunction "2_2") (pintype "passive"))
      (node (ref "E4") (pin "2") (pinfunction "2_2") (pintype "passive"))
      (node (ref "IC1") (pin "12") (pinfunction "AGND_12") (pintype "passive"))
      (node (ref "IC1") (pin "26") (pinfunction "PGND_26") (pintype "passive"))
      (node (ref "IC1") (pin "33") (pinfunction "GND_33") (pintype "passive"))
      (node (ref "J3") (pin "1") (pinfunction "1_1") (pintype "passive"))
      (node (ref "J4") (pin "1") (pinfunction "1_1") (pintype "passive"))
      (node (ref "J9") (pin "2") (pinfunction "2_2") (pintype "passive"))
      (node (ref "JP1") (pin "2") (pinfunction "2_2") (pintype "passive"))
      (node (ref "JP2") (pin "2") (pinfunction "2_2") (pintype "passive"))
      (node (ref "Q3") (pin "3") (pinfunction "S_3") (pintype "passive"))
      (node (ref "Q4") (pin "3") (pinfunction "S_3") (pintype "passive"))
      (node (ref "R15") (pin "2") (pinfunction "2_2") (pintype "passive"))
      (node (ref "R16") (pin "2") (pinfunction "2_2") (pintype "passive"))
      (node (ref "R22") (pin "2") (pinfunction "2_2") (pintype "passive"))
      (node (ref "R23") (pin "1") (pinfunction "1_1") (pintype "passive"))
      (node (ref "R25") (pin "2") (pinfunction "2_2") (pintype "passive"))
      (node (ref "R28") (pin "1") (pinfunction "1_1") (pintype "passive"))
      (node (ref "R33") (pin "1") (pinfunction "1_1") (pintype "passive"))
      (node (ref "SW1") (pin "1") (pinfunction "1_1") (pintype "passive"))
      (node (ref "SW1") (pin "4") (pinfunction "4_4") (pintype "passive"))
      (node (ref "SW2") (pin "1") (pinfunction "1_1") (pintype "passive"))
      (node (ref "SW2") (pin "4") (pinfunction "4_4") (pintype "passive"))
      (node (ref "SW3") (pin "1") (pinfunction "1_1") (pintype "passive"))
      (node (ref "SW3") (pin "4") (pinfunction "4_4") (pintype "passive"))
      (node (ref "SW4") (pin "1") (pinfunction "1_1") (pintype "passive"))
      (node (ref "SW4") (pin "4") (pinfunction "4_4") (pintype "passive"))
      (node (ref "U1") (pin "23") (pinfunction "VSS_1_23") (pintype "passive"))
      (node (ref "U1") (pin "35") (pinfunction "VSS_2_35") (pintype "passive"))
      (node (ref "U1") (pin "47") (pinfunction "VSS_3_47") (pintype "passive"))
      (node (ref "U1") (pin "8") (pinfunction "VSSA_8") (pintype "passive"))
      (node (ref "U2") (pin "1") (pinfunction "GND_1") (pintype "passive"))
    )
    (net (code "22") (name "Net-(C9-Pad2)") (class "Default")
      (node (ref "C9") (pin "2") (pinfunction "2_2") (pintype "passive"))
      (node (ref "R5") (pin "1") (pinfunction "1_1") (pintype "passive"))
    )
    (net (code "23") (name "Net-(C10-Pad2)") (class "Default")
      (node (ref "C10") (pin "2") (pinfunction "2_2") (pintype "passive"))
      (node (ref "R6") (pin "1") (pinfunction "1_1") (pintype "passive"))
    )
    (net (code "24") (name "Net-(C26-Pad1)") (class "Default")
      (node (ref "C26") (pin "1") (pinfunction "1_1") (pintype "passive"))
      (node (ref "R20") (pin "2") (pinfunction "2_2") (pintype "passive"))
    )
    (net (code "25") (name "Net-(IC1-BT1)") (class "Default")
      (node (ref "C22") (pin "2") (pinfunction "2_2") (pintype "passive"))
      (node (ref "IC1") (pin "30") (pinfunction "BT1_30") (pintype "passive"))
    )
    (net (code "26") (name "Net-(IC1-BT2)") (class "Default")
      (node (ref "C25") (pin "2") (pinfunction "2_2") (pintype "passive"))
      (node (ref "IC1") (pin "20") (pinfunction "BT2_20") (pintype "passive"))
    )
    (net (code "27") (name "Net-(IC1-COMP)") (class "Default")
      (node (ref "IC1") (pin "15") (pinfunction "COMP_15") (pintype "passive"))
      (node (ref "R20") (pin "1") (pinfunction "1_1") (pintype "passive"))
    )
    (net (code "28") (name "Net-(IC1-HD1)") (class "Default")
      (node (ref "IC1") (pin "29") (pinfunction "HD1_29") (pintype "passive"))
      (node (ref "J5") (pin "1") (pinfunction "1_1") (pintype "passive"))
      (node (ref "R3") (pin "2") (pinfunction "2_2") (pintype "passive"))
    )
    (net (code "29") (name "Net-(IC1-HD2)") (class "Default")
      (node (ref "IC1") (pin "21") (pinfunction "HD2_21") (pintype "passive"))
      (node (ref "J6") (pin "1") (pinfunction "1_1") (pintype "passive"))
      (node (ref "R4") (pin "1") (pinfunction "1_1") (pintype "passive"))
    )
    (net (code "30") (name "Net-(IC1-LD1)") (class "Default")
      (node (ref "IC1") (pin "27") (pinfunction "LD1_27") (pintype "passive"))
      (node (ref "J7") (pin "1") (pinfunction "1_1") (pintype "passive"))
      (node (ref "R11") (pin "2") (pinfunction "2_2") (pintype "passive"))
    )
    (net (code "31") (name "Net-(IC1-LD2)") (class "Default")
      (node (ref "IC1") (pin "23") (pinfunction "LD2_23") (pintype "passive"))
      (node (ref "J8") (pin "1") (pinfunction "1_1") (pintype "passive"))
      (node (ref "R12") (pin "1") (pinfunction "1_1") (pintype "passive"))
    )
    (net (code "32") (name "Net-(IC1-SNSE1N-_VIN)") (class "Default")
      (node (ref "C18") (pin "1") (pinfunction "1_1") (pintype "passive"))
      (node (ref "IC1") (pin "32") (pinfunction "SNSE1N-_VIN_32") (pintype "passive"))
      (node (ref "R8") (pin "1") (pinfunction "1_1") (pintype "passive"))
    )
    (net (code "33") (name "Net-(IC1-SNSE1P+_VIN)") (class "Default")
      (node (ref "C17") (pin "1") (pinfunction "1_1") (pintype "passive"))
      (node (ref "IC1") (pin "1") (pinfunction "SNSE1P+_VIN_1") (pintype "passive"))
      (node (ref "R7") (pin "1") (pinfunction "1_1") (pintype "passive"))
    )
    (net (code "34") (name "Net-(IC1-SW1)") (class "Default")
      (node (ref "C22") (pin "1") (pinfunction "1_1") (pintype "passive"))
      (node (ref "IC1") (pin "28") (pinfunction "SW1_28") (pintype "passive"))
      (node (ref "L1") (pin "1") (pinfunction "1_1") (pintype "passive"))
      (node (ref "Q1") (pin "3") (pinfunction "S_3") (pintype "passive"))
      (node (ref "Q4") (pin "2") (pinfunction "D_2") (pintype "passive"))
      (node (ref "R5") (pin "2") (pinfunction "2_2") (pintype "passive"))
    )
    (net (code "35") (name "Net-(IC1-SW2)") (class "Default")
      (node (ref "C25") (pin "1") (pinfunction "1_1") (pintype "passive"))
      (node (ref "IC1") (pin "22") (pinfunction "SW2_22") (pintype "passive"))
      (node (ref "L1") (pin "2") (pinfunction "2_2") (pintype "passive"))
      (node (ref "Q2") (pin "3") (pinfunction "S_3") (pintype "passive"))
      (node (ref "Q3") (pin "2") (pinfunction "D_2") (pintype "passive"))
      (node (ref "R6") (pin "2") (pinfunction "2_2") (pintype "passive"))
    )
    (net (code "36") (name "Net-(IC1-VBATS)") (class "Default")
      (node (ref "IC1") (pin "16") (pinfunction "VBATS_16") (pintype "passive"))
      (node (ref "R17") (pin "2") (pinfunction "2_2") (pintype "passive"))
      (node (ref "R22") (pin "1") (pinfunction "1_1") (pintype "passive"))
      (node (ref "RP1") (pin "2") (pinfunction "2_2") (pintype "passive"))
    )
    (net (code "37") (name "Net-(IC1-VOUT-SNS2N-)") (class "Default")
      (node (ref "C20") (pin "1") (pinfunction "1_1") (pintype "passive"))
      (node (ref "IC1") (pin "17") (pinfunction "VOUT-SNS2N-_17") (pintype "passive"))
      (node (ref "R10") (pin "1") (pinfunction "1_1") (pintype "passive"))
    )
    (net (code "38") (name "Net-(IC1-VOUT-SNS2P+)") (class "Default")
      (node (ref "C19") (pin "1") (pinfunction "1_1") (pintype "passive"))
      (node (ref "IC1") (pin "18") (pinfunction "VOUT-SNS2P+_18") (pintype "passive"))
      (node (ref "R9") (pin "1") (pinfunction "1_1") (pintype "passive"))
    )
    (net (code "39") (name "Net-(LED1-A)") (class "Default")
      (node (ref "LED1") (pin "1") (pinfunction "A_1") (pintype "passive"))
      (node (ref "R26") (pin "2") (pinfunction "2_2") (pintype "passive"))
    )
    (net (code "40") (name "Net-(Q1-D)") (class "Default")
      (node (ref "C7") (pin "1") (pinfunction "1_1") (pintype "passive"))
      (node (ref "Q1") (pin "2") (pinfunction "D_2") (pintype "passive"))
      (node (ref "R1") (pin "1") (pinfunction "1_1") (pintype "passive"))
      (node (ref "R8") (pin "2") (pinfunction "2_2") (pintype "passive"))
    )
    (net (code "41") (name "Net-(Q1-G)") (class "Default")
      (node (ref "Q1") (pin "1") (pinfunction "G_1") (pintype "passive"))
      (node (ref "R3") (pin "1") (pinfunction "1_1") (pintype "passive"))
    )
    (net (code "42") (name "Net-(Q2-D)") (class "Default")
      (node (ref "C8") (pin "2") (pinfunction "2_2") (pintype "passive"))
      (node (ref "Q2") (pin "2") (pinfunction "D_2") (pintype "passive"))
      (node (ref "R2") (pin "2") (pinfunction "2_2") (pintype "passive"))
      (node (ref "R9") (pin "2") (pinfunction "2_2") (pintype "passive"))
    )
    (net (code "43") (name "Net-(Q2-G)") (class "Default")
      (node (ref "Q2") (pin "1") (pinfunction "G_1") (pintype "passive"))
      (node (ref "R4") (pin "2") (pinfunction "2_2") (pintype "passive"))
    )
    (net (code "44") (name "Net-(Q3-G)") (class "Default")
      (node (ref "Q3") (pin "1") (pinfunction "G_1") (pintype "passive"))
      (node (ref "R12") (pin "2") (pinfunction "2_2") (pintype "passive"))
    )
    (net (code "45") (name "Net-(Q4-G)") (class "Default")
      (node (ref "Q4") (pin "1") (pinfunction "G_1") (pintype "passive"))
      (node (ref "R11") (pin "1") (pinfunction "1_1") (pintype "passive"))
    )
    (net (code "46") (name "Net-(U1-BOOT0)") (class "Default")
      (node (ref "R25") (pin "1") (pinfunction "1_1") (pintype "passive"))
      (node (ref "U1") (pin "44") (pinfunction "BOOT0_44") (pintype "passive"))
    )
    (net (code "47") (name "Net-(V1-ADJ)") (class "Default")
      (node (ref "R23") (pin "2") (pinfunction "2_2") (pintype "passive"))
      (node (ref "R24") (pin "1") (pinfunction "1_1") (pintype "passive"))
      (node (ref "V1") (pin "1") (pinfunction "ADJ_1") (pintype "passive"))
    )
    (net (code "48") (name "Net-(V2-ADJ)") (class "Default")
      (node (ref "R33") (pin "2") (pinfunction "2_2") (pintype "passive"))
      (node (ref "R34") (pin "1") (pinfunction "1_1") (pintype "passive"))
      (node (ref "V2") (pin "1") (pinfunction "ADJ_1") (pintype "passive"))
    )
    (net (code "49") (name "VBUS") (class "Default")
      (node (ref "R14") (pin "1") (pinfunction "1_1") (pintype "passive"))
    )
    (net (code "50") (name "VIN") (class "Default")
      (node (ref "C1") (pin "1") (pinfunction "1_1") (pintype "passive"))
      (node (ref "C11") (pin "2") (pinfunction "2_2") (pintype "passive"))
      (node (ref "C12") (pin "2") (pinfunction "2_2") (pintype "passive"))
      (node (ref "C13") (pin "2") (pinfunction "2_2") (pintype "passive"))
      (node (ref "C2") (pin "1") (pinfunction "1_1") (pintype "passive"))
      (node (ref "C23") (pin "1") (pinfunction "1_1") (pintype "passive"))
      (node (ref "C27") (pin "2") (pinfunction "2_2") (pintype "passive"))
      (node (ref "C28") (pin "2") (pinfunction "2_2") (pintype "passive"))
      (node (ref "C3") (pin "1") (pinfunction "1_1") (pintype "passive"))
      (node (ref "C7") (pin "2") (pinfunction "2_2") (pintype "passive"))
      (node (ref "E1") (pin "1") (pinfunction "1_1") (pintype "passive"))
      (node (ref "E2") (pin "1") (pinfunction "1_1") (pintype "passive"))
      (node (ref "IC1") (pin "31") (pinfunction "VIN_31") (pintype "passive"))
      (node (ref "J1") (pin "1") (pinfunction "1_1") (pintype "passive"))
      (node (ref "JP1") (pin "1") (pinfunction "1_1") (pintype "passive"))
      (node (ref "R1") (pin "2") (pinfunction "2_2") (pintype "passive"))
      (node (ref "R7") (pin "2") (pinfunction "2_2") (pintype "passive"))
      (node (ref "V1") (pin "3") (pinfunction "Vin_3") (pintype "passive"))
    )
    (net (code "51") (name "VOUT") (class "Default")
      (node (ref "C14") (pin "2") (pinfunction "2_2") (pintype "passive"))
      (node (ref "C15") (pin "2") (pinfunction "2_2") (pintype "passive"))
      (node (ref "C16") (pin "2") (pinfunction "2_2") (pintype "passive"))
      (node (ref "C4") (pin "1") (pinfunction "1_1") (pintype "passive"))
      (node (ref "C42") (pin "2") (pinfunction "2_2") (pintype "passive"))
      (node (ref "C43") (pin "2") (pinfunction "2_2") (pintype "passive"))
      (node (ref "C5") (pin "1") (pinfunction "1_1") (pintype "passive"))
      (node (ref "C6") (pin "1") (pinfunction "1_1") (pintype "passive"))
      (node (ref "C8") (pin "1") (pinfunction "1_1") (pintype "passive"))
      (node (ref "E3") (pin "1") (pinfunction "1_1") (pintype "passive"))
      (node (ref "E4") (pin "1") (pinfunction "1_1") (pintype "passive"))
      (node (ref "IC1") (pin "19") (pinfunction "VBAT_19") (pintype "passive"))
      (node (ref "J2") (pin "1") (pinfunction "1_1") (pintype "passive"))
      (node (ref "JP2") (pin "1") (pinfunction "1_1") (pintype "passive"))
      (node (ref "R10") (pin "2") (pinfunction "2_2") (pintype "passive"))
      (node (ref "R17") (pin "1") (pinfunction "1_1") (pintype "passive"))
      (node (ref "R2") (pin "1") (pinfunction "1_1") (pintype "passive"))
      (node (ref "RP1") (pin "3") (pinfunction "3_3") (pintype "passive"))
      (node (ref "V2") (pin "3") (pinfunction "Vin_3") (pintype "passive"))
    )
    (net (code "52") (name "unconnected-(IC1-ACIN-Pad6)") (class "Default")
      (node (ref "IC1") (pin "6") (pinfunction "ACIN_6") (pintype "passive+no_connect"))
    )
    (net (code "53") (name "unconnected-(IC1-CP-Pad3)") (class "Default")
      (node (ref "IC1") (pin "3") (pinfunction "CP_3") (pintype "passive+no_connect"))
    )
    (net (code "54") (name "unconnected-(IC1-GPIO-Pad2)") (class "Default")
      (node (ref "IC1") (pin "2") (pinfunction "GPIO_2") (pintype "passive+no_connect"))
    )
    (net (code "55") (name "unconnected-(IC1-INDET-Pad5)") (class "Default")
      (node (ref "IC1") (pin "5") (pinfunction "INDET_5") (pintype "passive+no_connect"))
    )
    (net (code "56") (name "unconnected-(IC1-PGATE{slash}DITHER-Pad4)") (class "Default")
      (node (ref "IC1") (pin "4") (pinfunction "PGATE/DITHER_4") (pintype "passive+no_connect"))
    )
    (net (code "57") (name "unconnected-(RP1-Pad1)") (class "Default")
      (node (ref "RP1") (pin "1") (pinfunction "1_1") (pintype "passive"))
    )
    (net (code "58") (name "unconnected-(U1-PA0{slash}WKUP{slash}ADC123_IN0{slash}T2C1ETR{slash}T5C1{slash}T8ETR-Pad10)") (class "Default")
      (node (ref "U1") (pin "10") (pinfunction "PA0/WKUP/ADC123_IN0/T2C1ETR/T5C1/T8ETR_10") (pintype "passive"))
    )
    (net (code "59") (name "unconnected-(U1-PA1{slash}ADC123_IN1{slash}T5C2{slash}T2C2-Pad11)") (class "Default")
      (node (ref "U1") (pin "11") (pinfunction "PA1/ADC123_IN1/T5C2/T2C2_11") (pintype "passive"))
    )
    (net (code "60") (name "unconnected-(U1-PA6{slash}ADC123_IN6{slash}SPI1_MISO{slash}T8T1BKIN{slash}T3C1-Pad16)") (class "Default")
      (node (ref "U1") (pin "16") (pinfunction "PA6/ADC123_IN6/SPI1_MISO/T8T1BKIN/T3C1_16") (pintype "passive"))
    )
    (net (code "61") (name "unconnected-(U1-PA7{slash}ADC123_IN7{slash}SPI1_MOSI{slash}T8C1N{slash}T3C2{slash}T1C1N-Pad17)") (class "Default")
      (node (ref "U1") (pin "17") (pinfunction "PA7/ADC123_IN7/SPI1_MOSI/T8C1N/T3C2/T1C1N_17") (pintype "passive"))
    )
    (net (code "62") (name "unconnected-(U1-PA8{slash}T1C1{slash}MCO-Pad29)") (class "Default")
      (node (ref "U1") (pin "29") (pinfunction "PA8/T1C1/MCO_29") (pintype "passive"))
    )
    (net (code "63") (name "unconnected-(U1-PA9{slash}T1C2{slash}USART1_Tx-Pad30)") (class "Default")
      (node (ref "U1") (pin "30") (pinfunction "PA9/T1C2/USART1_Tx_30") (pintype "passive"))
    )
    (net (code "64") (name "unconnected-(U1-PA10{slash}T1C3{slash}USART1_Rx-Pad31)") (class "Default")
      (node (ref "U1") (pin "31") (pinfunction "PA10/T1C3/USART1_Rx_31") (pintype "passive"))
    )
    (net (code "65") (name "unconnected-(U1-PA15{slash}JTDI{slash}I2S3_WS{slash}JTDI{slash}T2C1ETR{slash}SPI3_NSS-Pad38)") (class "Default")
      (node (ref "U1") (pin "38") (pinfunction "PA15/JTDI/I2S3_WS/JTDI/T2C1ETR/SPI3_NSS_38") (pintype "passive"))
    )
    (net (code "66") (name "unconnected-(U1-PB0{slash}ADC123_IN8{slash}T3C3{slash}T8C2N{slash}T1C2N-Pad18)") (class "Default")
      (node (ref "U1") (pin "18") (pinfunction "PB0/ADC123_IN8/T3C3/T8C2N/T1C2N_18") (pintype "passive"))
    )
    (net (code "67") (name "unconnected-(U1-PB1{slash}ADC123_IN9{slash}T3C4{slash}T8C3N{slash}T1C3N-Pad19)") (class "Default")
      (node (ref "U1") (pin "19") (pinfunction "PB1/ADC123_IN9/T3C4/T8C3N/T1C3N_19") (pintype "passive"))
    )
    (net (code "68") (name "unconnected-(U1-PB2{slash}BOOT1-Pad20)") (class "Default")
      (node (ref "U1") (pin "20") (pinfunction "PB2/BOOT1_20") (pintype "passive"))
    )
    (net (code "69") (name "unconnected-(U1-PB3{slash}JTDO{slash}SPI3_SCK{slash}I2S3_CK{slash}T2C2{slash}SPI1_SCK-Pad39)") (class "Default")
      (node (ref "U1") (pin "39") (pinfunction "PB3/JTDO/SPI3_SCK/I2S3_CK/T2C2/SPI1_SCK_39") (pintype "passive"))
    )
    (net (code "70") (name "unconnected-(U1-PB4{slash}NJTRST{slash}SPI3_MISO{slash}T3C1{slash}SPI1_MISO-Pad40)") (class "Default")
      (node (ref "U1") (pin "40") (pinfunction "PB4/NJTRST/SPI3_MISO/T3C1/SPI1_MISO_40") (pintype "passive"))
    )
    (net (code "71") (name "unconnected-(U1-PB5{slash}I2C1_SMBA{slash}I2S3_SD{slash}SPI3_MOSI{slash}T3C2{slash}SPI1_MOSI-Pad41)") (class "Default")
      (node (ref "U1") (pin "41") (pinfunction "PB5/I2C1_SMBA/I2S3_SD/SPI3_MOSI/T3C2/SPI1_MOSI_41") (pintype "passive"))
    )
    (net (code "72") (name "unconnected-(U1-PB10{slash}USART3_Tx{slash}I2C2_SCL{slash}T2C3-Pad21)") (class "Default")
      (node (ref "U1") (pin "21") (pinfunction "PB10/USART3_Tx/I2C2_SCL/T2C3_21") (pintype "passive"))
    )
    (net (code "73") (name "unconnected-(U1-PB11{slash}USART3_Rx{slash}I2C2_SDA{slash}T2C4-Pad22)") (class "Default")
      (node (ref "U1") (pin "22") (pinfunction "PB11/USART3_Rx/I2C2_SDA/T2C4_22") (pintype "passive"))
    )
    (net (code "74") (name "unconnected-(U1-PB13{slash}I2S2_CK{slash}T1CH1N{slash}SPI2_SCK-Pad26)") (class "Default")
      (node (ref "U1") (pin "26") (pinfunction "PB13/I2S2_CK/T1CH1N/SPI2_SCK_26") (pintype "passive"))
    )
    (net (code "75") (name "unconnected-(U1-PB14{slash}T1CH2N{slash}SPI2_MISO-Pad27)") (class "Default")
      (node (ref "U1") (pin "27") (pinfunction "PB14/T1CH2N/SPI2_MISO_27") (pintype "passive"))
    )
    (net (code "76") (name "unconnected-(U1-PB15{slash}I2S2_SD{slash}T1CH3N{slash}SPI2_MOSI-Pad28)") (class "Default")
      (node (ref "U1") (pin "28") (pinfunction "PB15/I2S2_SD/T1CH3N/SPI2_MOSI_28") (pintype "passive"))
    )
    (net (code "77") (name "unconnected-(U1-PC13-TAMPER-RTC-Pad2)") (class "Default")
      (node (ref "U1") (pin "2") (pinfunction "PC13-TAMPER-RTC_2") (pintype "passive"))
    )
    (net (code "78") (name "unconnected-(U1-PC14-OSC32_IN-Pad3)") (class "Default")
      (node (ref "U1") (pin "3") (pinfunction "PC14-OSC32_IN_3") (pintype "passive"))
    )
    (net (code "79") (name "unconnected-(U1-PC15-OSC32_OUT-Pad4)") (class "Default")
      (node (ref "U1") (pin "4") (pinfunction "PC15-OSC32_OUT_4") (pintype "passive"))
    )
  )
)
